# FPOSINDC3.net
KiCad netlist of a schematic drawn in Altium Designer
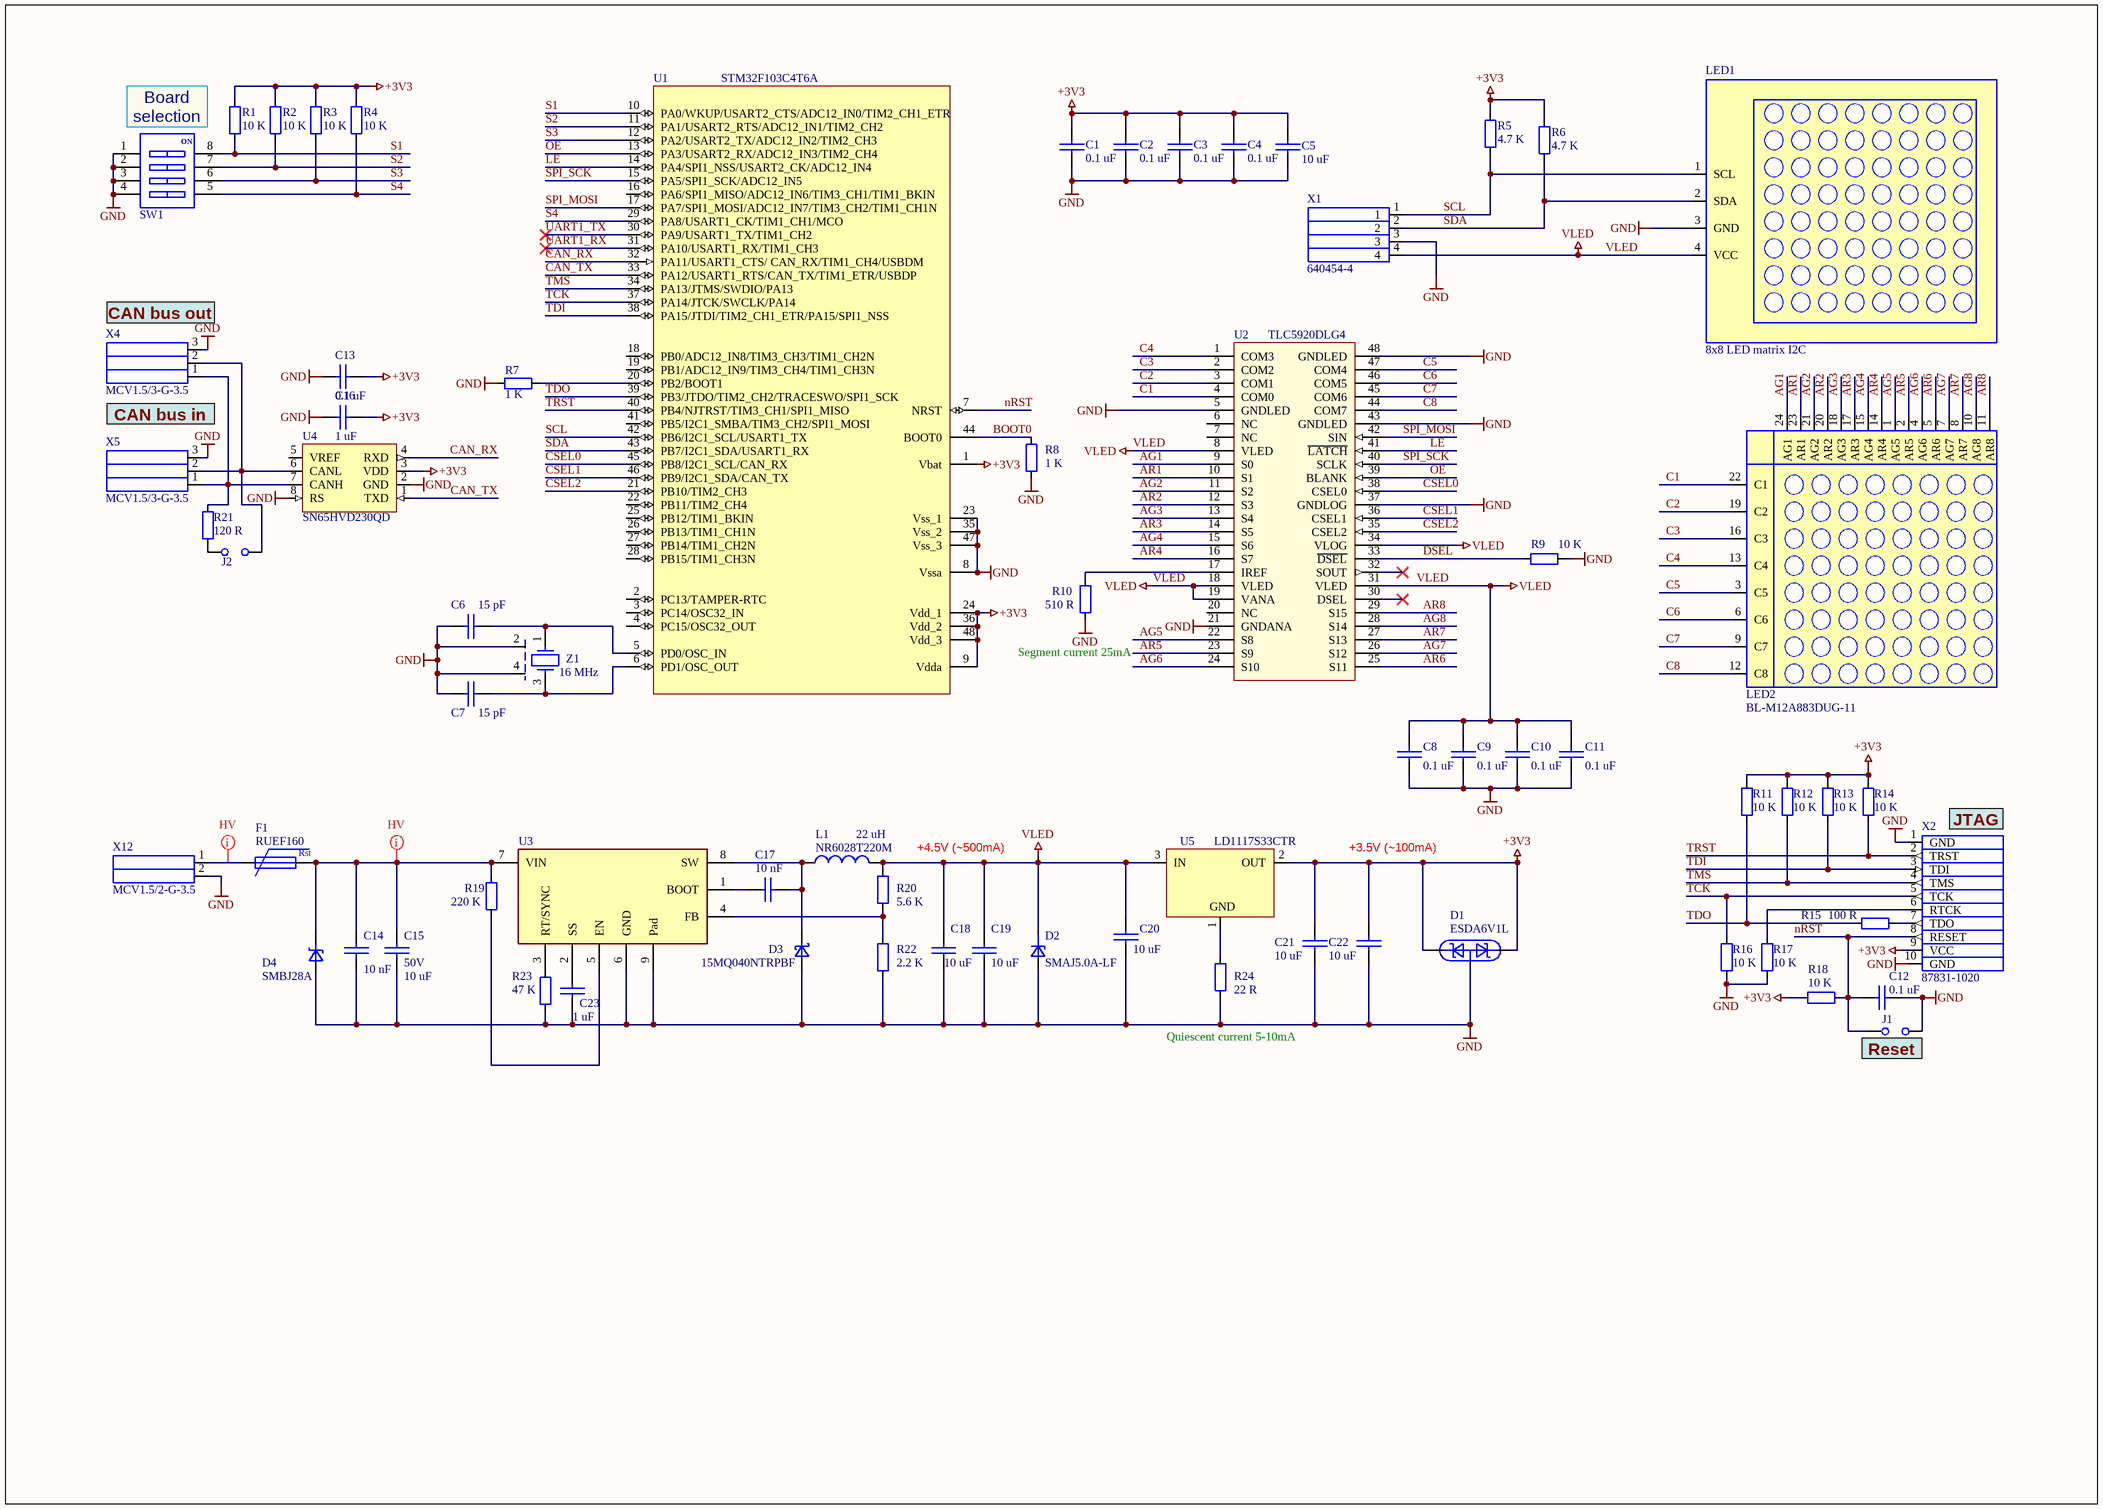
[diagram p0: FPOSINDC3.SchDoc]

(export (version "E")
  (design (tool "Eeschema 10.0.6"))
  (components
    (comp (ref "C1")
      (value "0.1 uF")
      (footprint "1608[0603]")
      (description "0.1 uF, 50V, 10% , X7R,  0603 SMD MLC Capacitor")
      (fields (field (name "TOLERANCE") "± 10%") (field (name "MANUFACTURER") "WALSIN"))
      (libsource (lib "ea_Capacitors") (part "CVNF100K0603-25"))
    )
    (comp (ref "C2")
      (value "0.1 uF")
      (footprint "1608[0603]")
      (description "0.1 uF, 50V, 10% , X7R,  0603 SMD MLC Capacitor")
      (fields (field (name "TOLERANCE") "± 10%") (field (name "MANUFACTURER") "WALSIN"))
      (libsource (lib "ea_Capacitors") (part "CVNF100K0603-25"))
    )
    (comp (ref "C3")
      (value "0.1 uF")
      (footprint "1608[0603]")
      (description "0.1 uF, 50V, 10% , X7R,  0603 SMD MLC Capacitor")
      (fields (field (name "TOLERANCE") "± 10%") (field (name "MANUFACTURER") "WALSIN"))
      (libsource (lib "ea_Capacitors") (part "CVNF100K0603-25"))
    )
    (comp (ref "C4")
      (value "0.1 uF")
      (footprint "1608[0603]")
      (description "0.1 uF, 50V, 10% , X7R,  0603 SMD MLC Capacitor")
      (fields (field (name "TOLERANCE") "± 10%") (field (name "MANUFACTURER") "WALSIN"))
      (libsource (lib "ea_Capacitors") (part "CVNF100K0603-25"))
    )
    (comp (ref "C5")
      (value "10 uF")
      (footprint "2012[0805]")
      (description "10 uF, 25V, X5R, ±10%, 0805")
      (fields (field (name "MANUFACTURER") "AVX Corporation") (field (name "TOLERANCE") "±10%"))
      (libsource (lib "ea_Capacitors") (part "GRM21BR60J106KE19L"))
    )
    (comp (ref "C6")
      (value "15 pF")
      (footprint "1608[0603]")
      (description "15 pF, 50V, 5%, NP0, 0603 SMD MLC Capacitor")
      (fields (field (name "MANUFACTURER") "Darfon") (field (name "TOLERANCE") "5%"))
      (libsource (lib "ea_Capacitors") (part "CCPF015K0603"))
    )
    (comp (ref "C7")
      (value "15 pF")
      (footprint "1608[0603]")
      (description "15 pF, 50V, 5%, NP0, 0603 SMD MLC Capacitor")
      (fields (field (name "MANUFACTURER") "Darfon") (field (name "TOLERANCE") "5%"))
      (libsource (lib "ea_Capacitors") (part "CCPF015K0603"))
    )
    (comp (ref "C8")
      (value "0.1 uF")
      (footprint "1608[0603]")
      (description "0.1 uF, 50V, 10% , X7R,  0603 SMD MLC Capacitor")
      (fields (field (name "TOLERANCE") "± 10%") (field (name "MANUFACTURER") "WALSIN"))
      (libsource (lib "ea_Capacitors") (part "CVNF100K0603-25"))
    )
    (comp (ref "C9")
      (value "0.1 uF")
      (footprint "1608[0603]")
      (description "0.1 uF, 50V, 10% , X7R,  0603 SMD MLC Capacitor")
      (fields (field (name "TOLERANCE") "± 10%") (field (name "MANUFACTURER") "WALSIN"))
      (libsource (lib "ea_Capacitors") (part "CVNF100K0603-25"))
    )
    (comp (ref "C10")
      (value "0.1 uF")
      (footprint "1608[0603]")
      (description "0.1 uF, 50V, 10% , X7R,  0603 SMD MLC Capacitor")
      (fields (field (name "TOLERANCE") "± 10%") (field (name "MANUFACTURER") "WALSIN"))
      (libsource (lib "ea_Capacitors") (part "CVNF100K0603-25"))
    )
    (comp (ref "C11")
      (value "0.1 uF")
      (footprint "1608[0603]")
      (description "0.1 uF, 50V, 10% , X7R,  0603 SMD MLC Capacitor")
      (fields (field (name "TOLERANCE") "± 10%") (field (name "MANUFACTURER") "WALSIN"))
      (libsource (lib "ea_Capacitors") (part "CVNF100K0603-25"))
    )
    (comp (ref "C12")
      (value "0.1 uF")
      (footprint "1608[0603]")
      (description "0.1 uF, 50V, 10% , X7R,  0603 SMD MLC Capacitor")
      (fields (field (name "TOLERANCE") "± 10%") (field (name "MANUFACTURER") "WALSIN"))
      (libsource (lib "ea_Capacitors") (part "CVNF100K0603-25"))
    )
    (comp (ref "C13")
      (value "0.1 uF")
      (footprint "1608[0603]")
      (description "0.1 uF, 50V, 10% , X7R,  0603 SMD MLC Capacitor")
      (fields (field (name "TOLERANCE") "± 10%") (field (name "MANUFACTURER") "WALSIN"))
      (libsource (lib "ea_Capacitors") (part "CVNF100K0603-25"))
    )
    (comp (ref "C14")
      (value "10 nF")
      (footprint "1608[0603]")
      (description "10 nF, 100V, 10%, X7R, 0603 SMD MLC Capacitor")
      (fields (field (name "MANUFACTURER") "SAMSUNG") (field (name "TOLERANCE") "±10%"))
      (libsource (lib "ea_Capacitors") (part "CVNF010K0603"))
    )
    (comp (ref "C15")
      (value "10 uF")
      (footprint "3225[1210]")
      (description "10uF, 50V, 20%, Y5V (F), 1210")
      (fields
        (field (name "MANUFACTURER") "Murata Electronics North America")
        (field (name "TOLERANCE") "20%")
        (field (name "VOLTAGE") "50V")
      )
      (libsource (lib "ea_Capacitors") (part "GRM32DF51H106ZA01L"))
    )
    (comp (ref "C16")
      (value "1 uF")
      (footprint "2012[0805]")
      (description "1 uF, 50V, 10%, X7R, 0805")
      (fields (field (name "MANUFACTURER") "KEMET") (field (name "TOLERANCE") "± 10%"))
      (libsource (lib "ea_Capacitors") (part "CVUF001K0805"))
    )
    (comp (ref "C17")
      (value "10 nF")
      (footprint "1608[0603]")
      (description "10 nF, 100V, 10%, X7R, 0603 SMD MLC Capacitor")
      (fields (field (name "TOLERANCE") "±10%") (field (name "MANUFACTURER") "SAMSUNG"))
      (libsource (lib "ea_Capacitors") (part "CVNF010K0603"))
    )
    (comp (ref "C18")
      (value "10 uF")
      (footprint "2012[0805]")
      (description "10 uF, 25V, X5R, ±10%, 0805")
      (fields (field (name "MANUFACTURER") "AVX Corporation") (field (name "TOLERANCE") "±10%"))
      (libsource (lib "ea_Capacitors") (part "LMK212F106ZG-T"))
    )
    (comp (ref "C19")
      (value "10 uF")
      (footprint "2012[0805]")
      (description "10 uF, 25V, X5R, ±10%, 0805")
      (fields (field (name "MANUFACTURER") "AVX Corporation") (field (name "TOLERANCE") "±10%"))
      (libsource (lib "ea_Capacitors") (part "LMK212F106ZG-T"))
    )
    (comp (ref "C20")
      (value "10 uF")
      (footprint "2012[0805]")
      (description "10 uF, 25V, X5R, ±10%, 0805")
      (fields (field (name "MANUFACTURER") "AVX Corporation") (field (name "TOLERANCE") "±10%"))
      (libsource (lib "ea_Capacitors") (part "LMK212F106ZG-T"))
    )
    (comp (ref "C21")
      (value "10 uF")
      (footprint "2012[0805]")
      (description "10 uF, 25V, X5R, ±10%, 0805")
      (fields (field (name "MANUFACTURER") "AVX Corporation") (field (name "TOLERANCE") "±10%"))
      (libsource (lib "ea_Capacitors") (part "LMK212F106ZG-T"))
    )
    (comp (ref "C22")
      (value "10 uF")
      (footprint "2012[0805]")
      (description "10 uF, 25V, X5R, ±10%, 0805")
      (fields (field (name "MANUFACTURER") "AVX Corporation") (field (name "TOLERANCE") "±10%"))
      (libsource (lib "ea_Capacitors") (part "LMK212F106ZG-T"))
    )
    (comp (ref "C23")
      (value "1 uF")
      (footprint "2012[0805]")
      (description "1 uF, 50V, 10%, X7R, 0805")
      (fields (field (name "MANUFACTURER") "KEMET") (field (name "TOLERANCE") "± 10%"))
      (libsource (lib "ea_Capacitors") (part "GRM21BR71A105KA01L"))
    )
    (comp (ref "D1")
      (value "ESDA6V1L")
      (footprint "SOT23")
      (description "Dual transil array for ESD, 6.1 V, 300 W")
      (fields (field (name "MANUFACTURER") "ST") (field (name "PARTNUM") "511-ESDA6V1L"))
      (libsource (lib "*") (part "ESDA6V1L"))
    )
    (comp (ref "D2")
      (value "SMAJ5.0A-LF")
      (footprint "DO-214AA_SMBJ")
      (description "TVS 400W 5.0V Unidirect")
      (fields (field (name "MANUFACTURER") "LITTELFUSE"))
      (libsource (lib "ea_TVS_protection") (part "SMAJ5.0A-LF"))
    )
    (comp (ref "D3")
      (value "15MQ040NTRPBF")
      (footprint "SMA")
      (description "Schottky Power Rectifier 3A, 40V, SMA")
      (fields (field (name "MANUFACTURER") "VISHAY"))
      (libsource (lib "ea_Diodes") (part "15MQ040N"))
    )
    (comp (ref "D4")
      (value "SMBJ28A")
      (footprint "DO-214AA_SMBJ")
      (description "DIODE TVS 28V 600W UNI 5% SMD")
      (fields (field (name "MANUFACTURER") "Littelfuse") (field (name "PARTNUM") "SMBJ28ABCT-ND"))
      (libsource (lib "ea_TVS_protection") (part "SMBJ28A"))
    )
    (comp (ref "F1")
      (value "RUEF160")
      (footprint "RUE160")
      (description "RUEF160 - POLYSWITCH, RADIAL, 1.6A")
      (fields (field (name "MANUFACTURER") "RAYCHEM") (field (name "PARTNUM") "RUEF160-ND"))
      (libsource (lib "ea_Fuses") (part "RUEF160"))
    )
    (comp (ref "J1")
      (value "Jumper")
      (footprint "HDR1X2V")
      (fields (field (name "MANUFACTURER") "NINIGI") (field (name "PARTNUM") "JUMPER-B"))
      (libsource (lib "ea_Commutation") (part "Jumper"))
    )
    (comp (ref "J2")
      (value "Jumper")
      (footprint "HDR1X2V")
      (fields (field (name "MANUFACTURER") "NINIGI") (field (name "PARTNUM") "JUMPER-B"))
      (libsource (lib "ea_Commutation") (part "Jumper"))
    )
    (comp (ref "L1")
      (value "NR6028T220M")
      (footprint "NR6028 yuden")
      (description "22uH, 1.3 A, 0.175 Ohms, +-20%,- 25 C to + 120 C")
      (fields
        (field (name "MANUFACTURER") "Taiyo Yuden")
        (field (name "PARTNUM") "587-2103-1-ND")
        (field (name "ALTIUM_VALUE") "22 uH")
      )
      (libsource (lib "ea_Inductors") (part "NR6028T220M"))
    )
    (comp (ref "LED1")
      (value "8x8 LED matrix I2C")
      (footprint "I2C 8x8 matrix adafruit 902")
      (description "Adafruit Bicolor LED Square Pixel Matrix with I2C Backpack")
      (fields (field (name "MANUFACTURER") "Adafruit") (field (name "PARTNUM") "ID: 902"))
      (libsource (lib "ea_Indicators") (part "8x8 LED matrix I2C"))
    )
    (comp (ref "LED2")
      (value "BL-M12A883DUG-11")
      (footprint "BL_M12A883DUG-11")
      (description "DOTMATRIX DISPLAY row catode red/green 8x8 31.7x31.7mm; Imax 30mA")
      (fields (field (name "MANUFACTURER") "BetLuxs"))
      (libsource (lib "ea_Indicators") (part "BL-M12A883DUG-11"))
    )
    (comp (ref "R1")
      (value "10 K")
      (footprint "0603")
      (description "10 K, 1%, 0603, SMD Resistor, Taped")
      (fields (field (name "MANUFACTURER") "YAGEO") (field (name "TOLERANCE") "± 1%"))
      (libsource (lib "") (part "RL0603K010-1_1"))
    )
    (comp (ref "R2")
      (value "10 K")
      (footprint "0603")
      (description "10 K, 1%, 0603, SMD Resistor, Taped")
      (fields (field (name "MANUFACTURER") "YAGEO") (field (name "TOLERANCE") "± 1%"))
      (libsource (lib "") (part "RL0603K010-1_1"))
    )
    (comp (ref "R3")
      (value "10 K")
      (footprint "0603")
      (description "10 K, 1%, 0603, SMD Resistor, Taped")
      (fields (field (name "MANUFACTURER") "YAGEO") (field (name "TOLERANCE") "± 1%"))
      (libsource (lib "") (part "RL0603K010-1_1"))
    )
    (comp (ref "R4")
      (value "10 K")
      (footprint "0603")
      (description "10 K, 1%, 0603, SMD Resistor, Taped")
      (fields (field (name "MANUFACTURER") "YAGEO") (field (name "TOLERANCE") "± 1%"))
      (libsource (lib "") (part "RL0603K010-1_1"))
    )
    (comp (ref "R5")
      (value "4.7 K")
      (footprint "0603")
      (description "4.7 K, 1%, 0603, SMD Resistor, Taped")
      (fields (field (name "MANUFACTURER") "Vishay") (field (name "TOLERANCE") "1%"))
      (libsource (lib "ea_Resistors") (part "RL0603K004.7-1"))
    )
    (comp (ref "R6")
      (value "4.7 K")
      (footprint "0603")
      (description "4.7 K, 1%, 0603, SMD Resistor, Taped")
      (fields (field (name "MANUFACTURER") "Vishay") (field (name "TOLERANCE") "1%"))
      (libsource (lib "ea_Resistors") (part "RL0603K004.7-1"))
    )
    (comp (ref "R7")
      (value "1 K")
      (footprint "0603")
      (description "1 K, 1%, 0603, SMD Resistor, Taped")
      (fields (field (name "MANUFACTURER") "Vishay") (field (name "TOLERANCE") "1%"))
      (libsource (lib "ea_Resistors") (part "RL0603K001-1"))
    )
    (comp (ref "R8")
      (value "1 K")
      (footprint "0603")
      (description "1 K, 1%, 0603, SMD Resistor, Taped")
      (fields (field (name "MANUFACTURER") "Vishay") (field (name "TOLERANCE") "1%"))
      (libsource (lib "") (part "RL0603K001-1_1"))
    )
    (comp (ref "R9")
      (value "10 K")
      (footprint "0603")
      (description "10 K, 1%, 0603, SMD Resistor, Taped")
      (fields (field (name "MANUFACTURER") "YAGEO") (field (name "TOLERANCE") "± 1%"))
      (libsource (lib "") (part "RL0603K010-1_2"))
    )
    (comp (ref "R10")
      (value "510 R")
      (footprint "0603")
      (description "510 R, 1%, 0603, SMD Resistor, Taped")
      (fields (field (name "MANUFACTURER") "Vishay") (field (name "TOLERANCE") "1%"))
      (libsource (lib "ea_Resistors") (part "RL0603E510-1"))
    )
    (comp (ref "R11")
      (value "10 K")
      (footprint "0603")
      (description "10 K, 1%, 0603, SMD Resistor, Taped")
      (fields (field (name "MANUFACTURER") "YAGEO") (field (name "TOLERANCE") "± 1%"))
      (libsource (lib "ea_Resistors") (part "RL0603K010-1"))
    )
    (comp (ref "R12")
      (value "10 K")
      (footprint "0603")
      (description "10 K, 1%, 0603, SMD Resistor, Taped")
      (fields (field (name "MANUFACTURER") "YAGEO") (field (name "TOLERANCE") "± 1%"))
      (libsource (lib "ea_Resistors") (part "RL0603K010-1"))
    )
    (comp (ref "R13")
      (value "10 K")
      (footprint "0603")
      (description "10 K, 1%, 0603, SMD Resistor, Taped")
      (fields (field (name "MANUFACTURER") "YAGEO") (field (name "TOLERANCE") "± 1%"))
      (libsource (lib "ea_Resistors") (part "RL0603K010-1"))
    )
    (comp (ref "R14")
      (value "10 K")
      (footprint "0603")
      (description "10 K, 1%, 0603, SMD Resistor, Taped")
      (fields (field (name "MANUFACTURER") "YAGEO") (field (name "TOLERANCE") "± 1%"))
      (libsource (lib "ea_Resistors") (part "RL0603K010-1"))
    )
    (comp (ref "R15")
      (value "100 R")
      (footprint "0603")
      (description "100 R, 1%, 0603, SMD Resistor, Taped")
      (fields (field (name "MANUFACTURER") "Vishay") (field (name "TOLERANCE") "1%"))
      (libsource (lib "ea_Resistors") (part "RL0603E100-1"))
    )
    (comp (ref "R16")
      (value "10 K")
      (footprint "0603")
      (description "10 K, 1%, 0603, SMD Resistor, Taped")
      (fields (field (name "MANUFACTURER") "YAGEO") (field (name "TOLERANCE") "± 1%"))
      (libsource (lib "ea_Resistors") (part "RL0603K010-1"))
    )
    (comp (ref "R17")
      (value "10 K")
      (footprint "0603")
      (description "10 K, 1%, 0603, SMD Resistor, Taped")
      (fields (field (name "MANUFACTURER") "YAGEO") (field (name "TOLERANCE") "± 1%"))
      (libsource (lib "ea_Resistors") (part "RL0603K010-1"))
    )
    (comp (ref "R18")
      (value "10 K")
      (footprint "0603")
      (description "10 K, 1%, 0603, SMD Resistor, Taped")
      (fields (field (name "MANUFACTURER") "YAGEO") (field (name "TOLERANCE") "± 1%"))
      (libsource (lib "") (part "RL0603K010-1_2"))
    )
    (comp (ref "R19")
      (value "220 K")
      (footprint "0603")
      (description "220 K, 1%, 0603, SMD Resistor, Taped")
      (fields (field (name "MANUFACTURER") "YAGEO AMERICA CORPORATION") (field (name "TOLERANCE") "1%"))
      (libsource (lib "ea_Resistors") (part "RL0603K220-1_1"))
    )
    (comp (ref "R20")
      (value "5.6 K")
      (footprint "0603")
      (description "5.6 K, 1%, 0603, SMD Resistor, Taped")
      (fields (field (name "MANUFACTURER") "Vishay") (field (name "TOLERANCE") "1%"))
      (libsource (lib "ea_Resistors") (part "RL0603K005.6-1"))
    )
    (comp (ref "R21")
      (value "120 R")
      (footprint "0603")
      (description "120 R, 1%, 0603, SMD Resistor, Taped")
      (fields (field (name "MANUFACTURER") "Vishay") (field (name "TOLERANCE") "1%"))
      (libsource (lib "ea_Resistors") (part "RL0603E120-1"))
    )
    (comp (ref "R22")
      (value "2.2 K")
      (footprint "0603")
      (description "2.2 K, 1%, 0603, SMD Resistor, Taped")
      (fields (field (name "MANUFACTURER") "Vishay") (field (name "TOLERANCE") "1%"))
      (libsource (lib "ea_Resistors") (part "RL0603K002.2-1"))
    )
    (comp (ref "R23")
      (value "47 K")
      (footprint "0603")
      (description "47 K, 1%, 0603, SMD Resistor, Taped")
      (fields (field (name "MANUFACTURER") "YAGEO AMERICA CORPORATION") (field (name "TOLERANCE") "1%"))
      (libsource (lib "ea_Resistors") (part "RC0603FR-0747KL"))
    )
    (comp (ref "R24")
      (value "22 R")
      (footprint "0603")
      (description "22 R, 1%, 0603, SMD Resistor, Taped")
      (fields (field (name "MANUFACTURER") "Vishay") (field (name "TOLERANCE") "1%"))
      (libsource (lib "ea_Resistors") (part "RL0603E022-1"))
    )
    (comp (ref "SW1")
      (value "MCDHN-04F-T-V")
      (footprint "MCDHN-04F-T-V")
      (description "SWITCH, DIP, SMD, 4 WAY, 1.27mm")
      (fields (field (name "MANUFACTURER") "MULTICOMP") (field (name "PARTNUM") "1605479"))
      (libsource (lib "ea_Commutation") (part "MCDHN-04F-T-V"))
    )
    (comp (ref "U1")
      (value "STM32F103C4T6A")
      (footprint "LQFP-48")
      (description "MCU ARM 32BIT 16K FLASH 48-LQFP")
      (fields (field (name "MANUFACTURER") "STMicroelectronics") (field (name "PARTNUM") "497-8316-ND"))
      (libsource (lib "ea_CPU") (part "STM32F103C4T6A"))
    )
    (comp (ref "U2")
      (value "TLC5920DLG4")
      (footprint "DL048")
      (description "16X8BIT LED DRIVER/CONTRLR, SSOP48")
      (fields (field (name "MANUFACTURER") "TI") (field (name "PARTNUM") "1226302"))
      (libsource (lib "ea_IC_registers_buffers") (part "TLC5920DLG4"))
    )
    (comp (ref "U3")
      (value "~")
      (footprint "SOIC-8 EDP")
      (description "SIMPLESWITCH, 1.0A 4.5~42VIN, 8PSOP, Vf 1.285")
      (fields (field (name "MANUFACTURER") "TI") (field (name "PARTNUM") "2323524"))
      (libsource (lib "ea_IC_Power_Reg_Ref_Sw") (part "LM22672MR-ADJ"))
    )
    (comp (ref "U4")
      (value "SN65HVD230QD")
      (footprint "SO-8")
      (description "3.3-V CAN TRANSCEIVERS SO-8")
      (fields (field (name "MANUFACTURER") "Texas Instruments") (field (name "PARTNUM") "296-13123-5-ND"))
      (libsource (lib "ea_IC_Interfaces") (part "SN65HVD230QD"))
    )
    (comp (ref "U5")
      (value "LD1117S33CTR")
      (footprint "SOT-223")
      (description "Low drop positive voltage regulator, 3.3 V, 1A, SOT-223")
      (fields (field (name "MANUFACTURER") "STMicroelectronics") (field (name "PARTNUM") "497-1241-1-ND"))
      (libsource (lib "ea_IC_Power_Reg_Ref_Sw") (part "LD1117S33CTR"))
    )
    (comp (ref "X1")
      (value "640454-4")
      (footprint "MTA-100 4-pos")
      (description "CONN HEADER VERT 4POS .100 TIN")
      (fields (field (name "MANUFACTURER") "TE Connectivity") (field (name "PARTNUM") "A19431-ND"))
      (libsource (lib "ea_Connectors") (part "640454-4"))
    )
    (comp (ref "X2")
      (value "87831-1020")
      (footprint "878311020 MGRID WALL HDR")
      (description "JTAG 2*5 2mm")
      (fields
        (field (name "MANUFACTURER") "Molex/Waldom Electronics Corp")
        (field (name "PARTNUM") "WM18560-ND")
      )
      (libsource (lib "ea_Connectors") (part "87831-1020"))
    )
    (comp (ref "X4")
      (value "MCV1.5/3-G-3.5")
      (footprint "mcv1.5-3-g_3.5")
      (description "HEADER, VERTICAL, 3.5MM, 3WAY")
      (fields (field (name "MANUFACTURER") "PHOENIX CONTACT") (field (name "PARTNUM") "3704828"))
      (libsource (lib "ea_Connectors") (part "MCV1.5/3-G-3.5"))
    )
    (comp (ref "X5")
      (value "MCV1.5/3-G-3.5")
      (footprint "mcv1.5-3-g_3.5")
      (description "HEADER, VERTICAL, 3.5MM, 3WAY")
      (fields (field (name "MANUFACTURER") "PHOENIX CONTACT") (field (name "PARTNUM") "3704828"))
      (libsource (lib "ea_Connectors") (part "MCV1.5/3-G-3.5"))
    )
    (comp (ref "X12")
      (value "MCV1.5/2-G-3.5")
      (footprint "mcv1.5-2-g_3.5")
      (description "HEADER, VERTICAL, 3.5MM, 2WAY")
      (fields (field (name "MANUFACTURER") "PHOENIX CONTACT") (field (name "PARTNUM") "3704816"))
      (libsource (lib "ea_Connectors") (part "MCV1.5/2-G-3.5"))
    )
    (comp (ref "Z1")
      (value "16 MHz")
      (footprint "DSX321G")
      (description "16 MHz, 8 pF, +-15 ppm, -10..+75 С")
      (fields (field (name "MANUFACTURER") "NDK") (field (name "PARTNUM") "644-1049-1-ND"))
      (libsource (lib "ea_OSC_CLK_GEN") (part "NX3225SA-16.0MHZ"))
    )
  )
  (nets
    (net (code "1") (name "+3V3") (class "Default")
      (node (ref "C1") (pin "2") (pinfunction "2_2") (pintype "passive"))
      (node (ref "C13") (pin "1") (pinfunction "1_1") (pintype "passive"))
      (node (ref "C16") (pin "1") (pinfunction "1_1") (pintype "passive"))
      (node (ref "C2") (pin "2") (pinfunction "2_2") (pintype "passive"))
      (node (ref "C21") (pin "2") (pinfunction "2_2") (pintype "passive"))
      (node (ref "C22") (pin "2") (pinfunction "2_2") (pintype "passive"))
      (node (ref "C3") (pin "2") (pinfunction "2_2") (pintype "passive"))
      (node (ref "C4") (pin "2") (pinfunction "2_2") (pintype "passive"))
      (node (ref "C5") (pin "2") (pinfunction "2_2") (pintype "passive"))
      (node (ref "D1") (pin "1") (pintype "passive"))
      (node (ref "D1") (pin "2") (pintype "passive"))
      (node (ref "R1") (pin "2") (pinfunction "2_2") (pintype "passive"))
      (node (ref "R11") (pin "1") (pinfunction "1_1") (pintype "passive"))
      (node (ref "R12") (pin "1") (pinfunction "1_1") (pintype "passive"))
      (node (ref "R13") (pin "1") (pinfunction "1_1") (pintype "passive"))
      (node (ref "R14") (pin "1") (pinfunction "1_1") (pintype "passive"))
      (node (ref "R18") (pin "1") (pinfunction "1_1") (pintype "passive"))
      (node (ref "R2") (pin "2") (pinfunction "2_2") (pintype "passive"))
      (node (ref "R3") (pin "2") (pinfunction "2_2") (pintype "passive"))
      (node (ref "R4") (pin "2") (pinfunction "2_2") (pintype "passive"))
      (node (ref "R5") (pin "1") (pinfunction "1_1") (pintype "passive"))
      (node (ref "R6") (pin "1") (pinfunction "1_1") (pintype "passive"))
      (node (ref "U1") (pin "1") (pinfunction "Vbat_1") (pintype "power_in"))
      (node (ref "U1") (pin "24") (pinfunction "Vdd_1_24") (pintype "power_in"))
      (node (ref "U1") (pin "36") (pinfunction "Vdd_2_36") (pintype "power_in"))
      (node (ref "U1") (pin "48") (pinfunction "Vdd_3_48") (pintype "power_in"))
      (node (ref "U1") (pin "9") (pinfunction "Vdda_9") (pintype "passive"))
      (node (ref "U4") (pin "3") (pinfunction "VDD_3") (pintype "power_in"))
      (node (ref "U5") (pin "2") (pinfunction "OUT_2") (pintype "power_in"))
      (node (ref "X2") (pin "9") (pinfunction "VCC_9") (pintype "power_in"))
    )
    (net (code "2") (name "/AG1") (class "Default")
      (node (ref "LED2") (pin "24") (pinfunction "AG1_24") (pintype "passive"))
      (node (ref "U2") (pin "9") (pinfunction "S0_9") (pintype "power_in"))
    )
    (net (code "3") (name "/AG2") (class "Default")
      (node (ref "LED2") (pin "21") (pinfunction "AG2_21") (pintype "passive"))
      (node (ref "U2") (pin "11") (pinfunction "S2_11") (pintype "power_in"))
    )
    (net (code "4") (name "/AG3") (class "Default")
      (node (ref "LED2") (pin "18") (pinfunction "AG3_18") (pintype "passive"))
      (node (ref "U2") (pin "13") (pinfunction "S4_13") (pintype "power_in"))
    )
    (net (code "5") (name "/AG4") (class "Default")
      (node (ref "LED2") (pin "15") (pinfunction "AG4_15") (pintype "passive"))
      (node (ref "U2") (pin "15") (pinfunction "S6_15") (pintype "power_in"))
    )
    (net (code "6") (name "/AG5") (class "Default")
      (node (ref "LED2") (pin "1") (pinfunction "AG5_1") (pintype "passive"))
      (node (ref "U2") (pin "22") (pinfunction "S8_22") (pintype "power_in"))
    )
    (net (code "7") (name "/AG6") (class "Default")
      (node (ref "LED2") (pin "4") (pinfunction "AG6_4") (pintype "passive"))
      (node (ref "U2") (pin "24") (pinfunction "S10_24") (pintype "power_in"))
    )
    (net (code "8") (name "/AG7") (class "Default")
      (node (ref "LED2") (pin "7") (pinfunction "AG7_7") (pintype "passive"))
      (node (ref "U2") (pin "26") (pinfunction "S12_26") (pintype "power_in"))
    )
    (net (code "9") (name "/AG8") (class "Default")
      (node (ref "LED2") (pin "10") (pinfunction "AG8_10") (pintype "passive"))
      (node (ref "U2") (pin "28") (pinfunction "S14_28") (pintype "power_in"))
    )
    (net (code "10") (name "/AR1") (class "Default")
      (node (ref "LED2") (pin "23") (pinfunction "AR1_23") (pintype "passive"))
      (node (ref "U2") (pin "10") (pinfunction "S1_10") (pintype "power_in"))
    )
    (net (code "11") (name "/AR2") (class "Default")
      (node (ref "LED2") (pin "20") (pinfunction "AR2_20") (pintype "passive"))
      (node (ref "U2") (pin "12") (pinfunction "S3_12") (pintype "power_in"))
    )
    (net (code "12") (name "/AR3") (class "Default")
      (node (ref "LED2") (pin "17") (pinfunction "AR3_17") (pintype "passive"))
      (node (ref "U2") (pin "14") (pinfunction "S5_14") (pintype "power_in"))
    )
    (net (code "13") (name "/AR4") (class "Default")
      (node (ref "LED2") (pin "14") (pinfunction "AR4_14") (pintype "passive"))
      (node (ref "U2") (pin "16") (pinfunction "S7_16") (pintype "power_in"))
    )
    (net (code "14") (name "/AR5") (class "Default")
      (node (ref "LED2") (pin "2") (pinfunction "AR5_2") (pintype "passive"))
      (node (ref "U2") (pin "23") (pinfunction "S9_23") (pintype "power_in"))
    )
    (net (code "15") (name "/AR6") (class "Default")
      (node (ref "LED2") (pin "5") (pinfunction "AR6_5") (pintype "passive"))
      (node (ref "U2") (pin "25") (pinfunction "S11_25") (pintype "power_in"))
    )
    (net (code "16") (name "/AR7") (class "Default")
      (node (ref "LED2") (pin "8") (pinfunction "AR7_8") (pintype "passive"))
      (node (ref "U2") (pin "27") (pinfunction "S13_27") (pintype "power_in"))
    )
    (net (code "17") (name "/AR8") (class "Default")
      (node (ref "LED2") (pin "11") (pinfunction "AR8_11") (pintype "passive"))
      (node (ref "U2") (pin "29") (pinfunction "S15_29") (pintype "power_in"))
    )
    (net (code "18") (name "/BOOT0") (class "Default")
      (node (ref "R8") (pin "2") (pinfunction "2_2") (pintype "passive"))
      (node (ref "U1") (pin "44") (pinfunction "BOOT0_44") (pintype "passive"))
    )
    (net (code "19") (name "/C1") (class "Default")
      (node (ref "LED2") (pin "22") (pinfunction "C1_22") (pintype "passive"))
      (node (ref "U2") (pin "4") (pinfunction "COM0_4") (pintype "power_in"))
    )
    (net (code "20") (name "/C2") (class "Default")
      (node (ref "LED2") (pin "19") (pinfunction "C2_19") (pintype "passive"))
      (node (ref "U2") (pin "3") (pinfunction "COM1_3") (pintype "power_in"))
    )
    (net (code "21") (name "/C3") (class "Default")
      (node (ref "LED2") (pin "16") (pinfunction "C3_16") (pintype "passive"))
      (node (ref "U2") (pin "2") (pinfunction "COM2_2") (pintype "power_in"))
    )
    (net (code "22") (name "/C4") (class "Default")
      (node (ref "LED2") (pin "13") (pinfunction "C4_13") (pintype "passive"))
      (node (ref "U2") (pin "1") (pinfunction "COM3_1") (pintype "power_in"))
    )
    (net (code "23") (name "/C5") (class "Default")
      (node (ref "LED2") (pin "3") (pinfunction "C5_3") (pintype "passive"))
      (node (ref "U2") (pin "47") (pinfunction "COM4_47") (pintype "power_in"))
    )
    (net (code "24") (name "/C6") (class "Default")
      (node (ref "LED2") (pin "6") (pinfunction "C6_6") (pintype "passive"))
      (node (ref "U2") (pin "46") (pinfunction "COM5_46") (pintype "power_in"))
    )
    (net (code "25") (name "/C7") (class "Default")
      (node (ref "LED2") (pin "9") (pinfunction "C7_9") (pintype "passive"))
      (node (ref "U2") (pin "45") (pinfunction "COM6_45") (pintype "power_in"))
    )
    (net (code "26") (name "/C8") (class "Default")
      (node (ref "LED2") (pin "12") (pinfunction "C8_12") (pintype "passive"))
      (node (ref "U2") (pin "44") (pinfunction "COM7_44") (pintype "power_in"))
    )
    (net (code "27") (name "/CAN_RX") (class "Default")
      (node (ref "U1") (pin "32") (pinfunction "PA11/USART1_CTS/_CAN_RX/TIM1_CH4/USBDM_32") (pintype "input"))
      (node (ref "U4") (pin "4") (pinfunction "RXD_4") (pintype "output"))
    )
    (net (code "28") (name "/CAN_TX") (class "Default")
      (node (ref "U1") (pin "33") (pinfunction "PA12/USART1_RTS/CAN_TX/TIM1_ETR/USBDP_33") (pintype "bidirectional"))
      (node (ref "U4") (pin "1") (pinfunction "TXD_1") (pintype "input"))
    )
    (net (code "29") (name "/CSEL0") (class "Default")
      (node (ref "U1") (pin "45") (pinfunction "PB8/I2C1_SCL/CAN_RX_45") (pintype "bidirectional"))
      (node (ref "U2") (pin "38") (pinfunction "CSEL0_38") (pintype "input"))
    )
    (net (code "30") (name "/CSEL1") (class "Default")
      (node (ref "U1") (pin "46") (pinfunction "PB9/I2C1_SDA/CAN_TX_46") (pintype "bidirectional"))
      (node (ref "U2") (pin "36") (pinfunction "CSEL1_36") (pintype "input"))
    )
    (net (code "31") (name "/CSEL2") (class "Default")
      (node (ref "U1") (pin "21") (pinfunction "PB10/TIM2_CH3_21") (pintype "bidirectional"))
      (node (ref "U2") (pin "35") (pinfunction "CSEL2_35") (pintype "input"))
    )
    (net (code "32") (name "/DSEL") (class "Default")
      (node (ref "R9") (pin "1") (pinfunction "1_1") (pintype "passive"))
      (node (ref "U2") (pin "33") (pinfunction "~{DSEL}_33") (pintype "passive"))
    )
    (net (code "33") (name "/LE") (class "Default")
      (node (ref "U1") (pin "14") (pinfunction "PA4/SPI1_NSS/USART2_CK/ADC12_IN4_14") (pintype "bidirectional"))
      (node (ref "U2") (pin "41") (pinfunction "~{LATCH}_41") (pintype "input"))
    )
    (net (code "34") (name "/OE") (class "Default")
      (node (ref "U1") (pin "13") (pinfunction "PA3/USART2_RX/ADC12_IN3/TIM2_CH4_13") (pintype "bidirectional"))
      (node (ref "U2") (pin "39") (pinfunction "BLANK_39") (pintype "input"))
    )
    (net (code "35") (name "/S1") (class "Default")
      (node (ref "R1") (pin "1") (pinfunction "1_1") (pintype "passive"))
      (node (ref "SW1") (pin "8") (pinfunction "8_8") (pintype "passive"))
      (node (ref "U1") (pin "10") (pinfunction "PA0/WKUP/USART2_CTS/ADC12_IN0/TIM2_CH1_ETR_10") (pintype "bidirectional"))
    )
    (net (code "36") (name "/S2") (class "Default")
      (node (ref "R2") (pin "1") (pinfunction "1_1") (pintype "passive"))
      (node (ref "SW1") (pin "7") (pinfunction "7_7") (pintype "passive"))
      (node (ref "U1") (pin "11") (pinfunction "PA1/USART2_RTS/ADC12_IN1/TIM2_CH2_11") (pintype "bidirectional"))
    )
    (net (code "37") (name "/S3") (class "Default")
      (node (ref "R3") (pin "1") (pinfunction "1_1") (pintype "passive"))
      (node (ref "SW1") (pin "6") (pinfunction "6_6") (pintype "passive"))
      (node (ref "U1") (pin "12") (pinfunction "PA2/USART2_TX/ADC12_IN2/TIM2_CH3_12") (pintype "bidirectional"))
    )
    (net (code "38") (name "/S4") (class "Default")
      (node (ref "R4") (pin "1") (pinfunction "1_1") (pintype "passive"))
      (node (ref "SW1") (pin "5") (pinfunction "5_5") (pintype "passive"))
      (node (ref "U1") (pin "29") (pinfunction "PA8/USART1_CK/TIM1_CH1/MCO_29") (pintype "bidirectional"))
    )
    (net (code "39") (name "/SCL") (class "Default")
      (node (ref "LED1") (pin "1") (pinfunction "SCL_1") (pintype "passive"))
      (node (ref "R5") (pin "2") (pinfunction "2_2") (pintype "passive"))
      (node (ref "U1") (pin "42") (pinfunction "PB6/I2C1_SCL/USART1_TX_42") (pintype "bidirectional"))
      (node (ref "X1") (pin "1") (pinfunction "1_1") (pintype "passive"))
    )
    (net (code "40") (name "/SDA") (class "Default")
      (node (ref "LED1") (pin "2") (pinfunction "SDA_2") (pintype "passive"))
      (node (ref "R6") (pin "2") (pinfunction "2_2") (pintype "passive"))
      (node (ref "U1") (pin "43") (pinfunction "PB7/I2C1_SDA/USART1_RX_43") (pintype "bidirectional"))
      (node (ref "X1") (pin "2") (pinfunction "2_2") (pintype "passive"))
    )
    (net (code "41") (name "/SPI_MOSI") (class "Default")
      (node (ref "U1") (pin "17") (pinfunction "PA7/SPI1_MOSI/ADC12_IN7/TIM3_CH2/TIM1_CH1N_17") (pintype "bidirectional"))
      (node (ref "U2") (pin "42") (pinfunction "SIN_42") (pintype "input"))
    )
    (net (code "42") (name "/SPI_SCK") (class "Default")
      (node (ref "U1") (pin "15") (pinfunction "PA5/SPI1_SCK/ADC12_IN5_15") (pintype "bidirectional"))
      (node (ref "U2") (pin "40") (pinfunction "SCLK_40") (pintype "input"))
    )
    (net (code "43") (name "/TCK") (class "Default")
      (node (ref "R16") (pin "1") (pinfunction "1_1") (pintype "passive"))
      (node (ref "U1") (pin "37") (pinfunction "PA14/JTCK/SWCLK/PA14_37") (pintype "bidirectional"))
      (node (ref "X2") (pin "5") (pinfunction "TCK_5") (pintype "output"))
    )
    (net (code "44") (name "/TDI") (class "Default")
      (node (ref "R13") (pin "2") (pinfunction "2_2") (pintype "passive"))
      (node (ref "U1") (pin "38") (pinfunction "PA15/JTDI/TIM2_CH1_ETR/PA15/SPI1_NSS_38") (pintype "bidirectional"))
      (node (ref "X2") (pin "3") (pinfunction "TDI_3") (pintype "input"))
    )
    (net (code "45") (name "/TDO") (class "Default")
      (node (ref "R11") (pin "2") (pinfunction "2_2") (pintype "passive"))
      (node (ref "R15") (pin "1") (pinfunction "1_1") (pintype "passive"))
      (node (ref "U1") (pin "39") (pinfunction "PB3/JTDO/TIM2_CH2/TRACESWO/SPI1_SCK_39") (pintype "bidirectional"))
    )
    (net (code "46") (name "/TMS") (class "Default")
      (node (ref "R12") (pin "2") (pinfunction "2_2") (pintype "passive"))
      (node (ref "U1") (pin "34") (pinfunction "PA13/JTMS/SWDIO/PA13_34") (pintype "bidirectional"))
      (node (ref "X2") (pin "4") (pinfunction "TMS_4") (pintype "output"))
    )
    (net (code "47") (name "/TRST") (class "Default")
      (node (ref "R14") (pin "2") (pinfunction "2_2") (pintype "passive"))
      (node (ref "U1") (pin "40") (pinfunction "PB4/NJTRST/TIM3_CH1/SPI1_MISO_40") (pintype "bidirectional"))
      (node (ref "X2") (pin "2") (pinfunction "TRST_2") (pintype "output"))
    )
    (net (code "48") (name "/UART1_RX") (class "Default")
      (node (ref "U1") (pin "31") (pinfunction "PA10/USART1_RX/TIM1_CH3_31") (pintype "bidirectional+no_connect"))
    )
    (net (code "49") (name "/UART1_TX") (class "Default")
      (node (ref "U1") (pin "30") (pinfunction "PA9/USART1_TX/TIM1_CH2_30") (pintype "bidirectional+no_connect"))
    )
    (net (code "50") (name "/nRST") (class "Default")
      (node (ref "C12") (pin "1") (pinfunction "1_1") (pintype "passive"))
      (node (ref "J1") (pin "1") (pinfunction "1_1") (pintype "passive"))
      (node (ref "R18") (pin "2") (pinfunction "2_2") (pintype "passive"))
      (node (ref "U1") (pin "7") (pinfunction "NRST_7") (pintype "bidirectional"))
      (node (ref "X2") (pin "8") (pinfunction "RESET_8") (pintype "output"))
    )
    (net (code "51") (name "GND") (class "Default")
      (node (ref "C1") (pin "1") (pinfunction "1_1") (pintype "passive"))
      (node (ref "C10") (pin "1") (pinfunction "1_1") (pintype "passive"))
      (node (ref "C11") (pin "1") (pinfunction "1_1") (pintype "passive"))
      (node (ref "C12") (pin "2") (pinfunction "2_2") (pintype "passive"))
      (node (ref "C13") (pin "2") (pinfunction "2_2") (pintype "passive"))
      (node (ref "C14") (pin "2") (pinfunction "2_2") (pintype "passive"))
      (node (ref "C15") (pin "2") (pinfunction "2_2") (pintype "passive"))
      (node (ref "C16") (pin "2") (pinfunction "2_2") (pintype "passive"))
      (node (ref "C18") (pin "1") (pinfunction "1_1") (pintype "passive"))
      (node (ref "C19") (pin "1") (pinfunction "1_1") (pintype "passive"))
      (node (ref "C2") (pin "1") (pinfunction "1_1") (pintype "passive"))
      (node (ref "C20") (pin "1") (pinfunction "1_1") (pintype "passive"))
      (node (ref "C21") (pin "1") (pinfunction "1_1") (pintype "passive"))
      (node (ref "C22") (pin "1") (pinfunction "1_1") (pintype "passive"))
      (node (ref "C23") (pin "1") (pinfunction "1_1") (pintype "passive"))
      (node (ref "C3") (pin "1") (pinfunction "1_1") (pintype "passive"))
      (node (ref "C4") (pin "1") (pinfunction "1_1") (pintype "passive"))
      (node (ref "C5") (pin "1") (pinfunction "1_1") (pintype "passive"))
      (node (ref "C6") (pin "2") (pinfunction "2_2") (pintype "passive"))
      (node (ref "C7") (pin "1") (pinfunction "1_1") (pintype "passive"))
      (node (ref "C8") (pin "1") (pinfunction "1_1") (pintype "passive"))
      (node (ref "C9") (pin "1") (pinfunction "1_1") (pintype "passive"))
      (node (ref "D1") (pin "3") (pintype "passive"))
      (node (ref "D2") (pin "2") (pinfunction "A_2") (pintype "passive"))
      (node (ref "D3") (pin "A") (pinfunction "A_A") (pintype "passive"))
      (node (ref "D4") (pin "2") (pinfunction "A_2") (pintype "passive"))
      (node (ref "J1") (pin "2") (pinfunction "2_2") (pintype "passive"))
      (node (ref "LED1") (pin "3") (pinfunction "GND_3") (pintype "passive"))
      (node (ref "R10") (pin "1") (pinfunction "1_1") (pintype "passive"))
      (node (ref "R16") (pin "2") (pinfunction "2_2") (pintype "passive"))
      (node (ref "R17") (pin "2") (pinfunction "2_2") (pintype "passive"))
      (node (ref "R22") (pin "1") (pinfunction "1_1") (pintype "passive"))
      (node (ref "R23") (pin "1") (pinfunction "1_1") (pintype "passive"))
      (node (ref "R24") (pin "1") (pinfunction "1_1") (pintype "passive"))
      (node (ref "R7") (pin "1") (pinfunction "1_1") (pintype "passive"))
      (node (ref "R8") (pin "1") (pinfunction "1_1") (pintype "passive"))
      (node (ref "R9") (pin "2") (pinfunction "2_2") (pintype "passive"))
      (node (ref "SW1") (pin "1") (pinfunction "1_1") (pintype "passive"))
      (node (ref "SW1") (pin "2") (pinfunction "2_2") (pintype "passive"))
      (node (ref "SW1") (pin "3") (pinfunction "3_3") (pintype "passive"))
      (node (ref "SW1") (pin "4") (pinfunction "4_4") (pintype "passive"))
      (node (ref "U1") (pin "23") (pinfunction "Vss_1_23") (pintype "power_in"))
      (node (ref "U1") (pin "35") (pinfunction "Vss_2_35") (pintype "power_in"))
      (node (ref "U1") (pin "47") (pinfunction "Vss_3_47") (pintype "power_in"))
      (node (ref "U1") (pin "8") (pinfunction "Vssa_8") (pintype "power_in"))
      (node (ref "U2") (pin "21") (pinfunction "GNDANA_21") (pintype "power_in"))
      (node (ref "U2") (pin "37") (pinfunction "GNDLOG_37") (pintype "power_in"))
      (node (ref "U2") (pin "43") (pinfunction "GNDLED_43") (pintype "power_in"))
      (node (ref "U2") (pin "48") (pinfunction "GNDLED_48") (pintype "power_in"))
      (node (ref "U2") (pin "5") (pinfunction "GNDLED_5") (pintype "power_in"))
      (node (ref "U3") (pin "6") (pinfunction "GND_6") (pintype "passive"))
      (node (ref "U3") (pin "9") (pinfunction "Pad_9") (pintype "passive"))
      (node (ref "U4") (pin "2") (pinfunction "GND_2") (pintype "power_in"))
      (node (ref "U4") (pin "8") (pinfunction "RS_8") (pintype "input"))
      (node (ref "X1") (pin "3") (pinfunction "3_3") (pintype "passive"))
      (node (ref "X12") (pin "2") (pinfunction "2_2") (pintype "passive"))
      (node (ref "X2") (pin "1") (pinfunction "GND_1") (pintype "power_in"))
      (node (ref "X2") (pin "10") (pinfunction "GND_10") (pintype "power_in"))
      (node (ref "X4") (pin "3") (pinfunction "3_3") (pintype "passive"))
      (node (ref "X5") (pin "3") (pinfunction "3_3") (pintype "passive"))
      (node (ref "Z1") (pin "2") (pinfunction "2_2") (pintype "passive"))
      (node (ref "Z1") (pin "4") (pinfunction "4_4") (pintype "passive"))
    )
    (net (code "52") (name "Net-(D4-C)") (class "Default")
      (node (ref "C14") (pin "1") (pinfunction "1_1") (pintype "passive"))
      (node (ref "C15") (pin "1") (pinfunction "1_1") (pintype "passive"))
      (node (ref "D4") (pin "1") (pinfunction "C_1") (pintype "passive"))
      (node (ref "F1") (pin "2") (pinfunction "2_2") (pintype "passive"))
      (node (ref "R19") (pin "2") (pinfunction "2_2") (pintype "passive"))
      (node (ref "U3") (pin "7") (pinfunction "VIN_7") (pintype "passive"))
    )
    (net (code "53") (name "Net-(F1-Pad1)") (class "Default")
      (node (ref "F1") (pin "1") (pinfunction "1_1") (pintype "passive"))
      (node (ref "X12") (pin "1") (pinfunction "1_1") (pintype "passive"))
    )
    (net (code "54") (name "Net-(J2-Pad2)") (class "Default")
      (node (ref "J2") (pin "2") (pinfunction "2_2") (pintype "passive"))
      (node (ref "R21") (pin "1") (pinfunction "1_1") (pintype "passive"))
    )
    (net (code "55") (name "Net-(U1-PB2{slash}BOOT1)") (class "Default")
      (node (ref "R7") (pin "2") (pinfunction "2_2") (pintype "passive"))
      (node (ref "U1") (pin "20") (pinfunction "PB2/BOOT1_20") (pintype "bidirectional"))
    )
    (net (code "56") (name "Net-(U1-PD0{slash}OSC_IN)") (class "Default")
      (node (ref "C6") (pin "1") (pinfunction "1_1") (pintype "passive"))
      (node (ref "U1") (pin "5") (pinfunction "PD0/OSC_IN_5") (pintype "bidirectional"))
      (node (ref "Z1") (pin "1") (pinfunction "1_1") (pintype "passive"))
    )
    (net (code "57") (name "Net-(U1-PD1{slash}OSC_OUT)") (class "Default")
      (node (ref "C7") (pin "2") (pinfunction "2_2") (pintype "passive"))
      (node (ref "U1") (pin "6") (pinfunction "PD1/OSC_OUT_6") (pintype "bidirectional"))
      (node (ref "Z1") (pin "3") (pinfunction "3_3") (pintype "passive"))
    )
    (net (code "58") (name "Net-(U2-IREF)") (class "Default")
      (node (ref "R10") (pin "2") (pinfunction "2_2") (pintype "passive"))
      (node (ref "U2") (pin "17") (pinfunction "IREF_17") (pintype "power_in"))
    )
    (net (code "59") (name "Net-(U3-BOOT)") (class "Default")
      (node (ref "C17") (pin "2") (pinfunction "2_2") (pintype "passive"))
      (node (ref "U3") (pin "1") (pinfunction "BOOT_1") (pintype "passive"))
    )
    (net (code "60") (name "Net-(U3-EN)") (class "Default")
      (node (ref "R19") (pin "1") (pinfunction "1_1") (pintype "passive"))
      (node (ref "U3") (pin "5") (pinfunction "EN_5") (pintype "passive"))
    )
    (net (code "61") (name "Net-(U3-FB)") (class "Default")
      (node (ref "R20") (pin "1") (pinfunction "1_1") (pintype "passive"))
      (node (ref "R22") (pin "2") (pinfunction "2_2") (pintype "passive"))
      (node (ref "U3") (pin "4") (pinfunction "FB_4") (pintype "passive"))
    )
    (net (code "62") (name "Net-(U3-RT{slash}SYNC)") (class "Default")
      (node (ref "R23") (pin "2") (pinfunction "2_2") (pintype "passive"))
      (node (ref "U3") (pin "3") (pinfunction "RT/SYNC_3") (pintype "passive"))
    )
    (net (code "63") (name "Net-(U3-SS)") (class "Default")
      (node (ref "C23") (pin "2") (pinfunction "2_2") (pintype "passive"))
      (node (ref "U3") (pin "2") (pinfunction "SS_2") (pintype "passive"))
    )
    (net (code "64") (name "Net-(U3-SW)") (class "Default")
      (node (ref "C17") (pin "1") (pinfunction "1_1") (pintype "passive"))
      (node (ref "D3") (pin "K") (pinfunction "K_K") (pintype "passive"))
      (node (ref "L1") (pin "1") (pinfunction "1_1") (pintype "passive"))
      (node (ref "U3") (pin "8") (pinfunction "SW_8") (pintype "passive"))
    )
    (net (code "65") (name "Net-(U4-CANH)") (class "Default")
      (node (ref "R21") (pin "2") (pinfunction "2_2") (pintype "passive"))
      (node (ref "U4") (pin "7") (pinfunction "CANH_7") (pintype "bidirectional"))
      (node (ref "X4") (pin "1") (pinfunction "1_1") (pintype "passive"))
      (node (ref "X5") (pin "1") (pinfunction "1_1") (pintype "passive"))
    )
    (net (code "66") (name "Net-(U4-CANL)") (class "Default")
      (node (ref "J2") (pin "1") (pinfunction "1_1") (pintype "passive"))
      (node (ref "U4") (pin "6") (pinfunction "CANL_6") (pintype "bidirectional"))
      (node (ref "X4") (pin "2") (pinfunction "2_2") (pintype "passive"))
      (node (ref "X5") (pin "2") (pinfunction "2_2") (pintype "passive"))
    )
    (net (code "67") (name "Net-(U5-GND)") (class "Default")
      (node (ref "R24") (pin "2") (pinfunction "2_2") (pintype "passive"))
      (node (ref "U5") (pin "1") (pinfunction "GND_1") (pintype "power_in"))
    )
    (net (code "68") (name "Net-(X2-RTCK)") (class "Default")
      (node (ref "R17") (pin "1") (pinfunction "1_1") (pintype "passive"))
      (node (ref "X2") (pin "6") (pinfunction "RTCK_6") (pintype "passive"))
    )
    (net (code "69") (name "Net-(X2-TDO)") (class "Default")
      (node (ref "R15") (pin "2") (pinfunction "2_2") (pintype "passive"))
      (node (ref "X2") (pin "7") (pinfunction "TDO_7") (pintype "output"))
    )
    (net (code "70") (name "VLED") (class "Default")
      (node (ref "C10") (pin "2") (pinfunction "2_2") (pintype "passive"))
      (node (ref "C11") (pin "2") (pinfunction "2_2") (pintype "passive"))
      (node (ref "C18") (pin "2") (pinfunction "2_2") (pintype "passive"))
      (node (ref "C19") (pin "2") (pinfunction "2_2") (pintype "passive"))
      (node (ref "C20") (pin "2") (pinfunction "2_2") (pintype "passive"))
      (node (ref "C8") (pin "2") (pinfunction "2_2") (pintype "passive"))
      (node (ref "C9") (pin "2") (pinfunction "2_2") (pintype "passive"))
      (node (ref "D2") (pin "1") (pinfunction "C_1") (pintype "passive"))
      (node (ref "L1") (pin "2") (pinfunction "2_2") (pintype "passive"))
      (node (ref "LED1") (pin "4") (pinfunction "VCC_4") (pintype "passive"))
      (node (ref "R20") (pin "2") (pinfunction "2_2") (pintype "passive"))
      (node (ref "U2") (pin "18") (pinfunction "VLED_18") (pintype "power_in"))
      (node (ref "U2") (pin "19") (pinfunction "VANA_19") (pintype "power_in"))
      (node (ref "U2") (pin "31") (pinfunction "VLED_31") (pintype "power_in"))
      (node (ref "U2") (pin "34") (pinfunction "VLOG_34") (pintype "power_in"))
      (node (ref "U2") (pin "8") (pinfunction "VLED_8") (pintype "power_in"))
      (node (ref "U5") (pin "3") (pinfunction "IN_3") (pintype "power_in"))
      (node (ref "X1") (pin "4") (pinfunction "4_4") (pintype "passive"))
    )
    (net (code "71") (name "unconnected-(U1-PA6{slash}SPI1_MISO{slash}ADC12_IN6{slash}TIM3_CH1{slash}TIM1_BKIN-Pad16)") (class "Default")
      (node (ref "U1") (pin "16") (pinfunction "PA6/SPI1_MISO/ADC12_IN6/TIM3_CH1/TIM1_BKIN_16") (pintype "bidirectional"))
    )
    (net (code "72") (name "unconnected-(U1-PB0{slash}ADC12_IN8{slash}TIM3_CH3{slash}TIM1_CH2N-Pad18)") (class "Default")
      (node (ref "U1") (pin "18") (pinfunction "PB0/ADC12_IN8/TIM3_CH3/TIM1_CH2N_18") (pintype "bidirectional"))
    )
    (net (code "73") (name "unconnected-(U1-PB1{slash}ADC12_IN9{slash}TIM3_CH4{slash}TIM1_CH3N-Pad19)") (class "Default")
      (node (ref "U1") (pin "19") (pinfunction "PB1/ADC12_IN9/TIM3_CH4/TIM1_CH3N_19") (pintype "bidirectional"))
    )
    (net (code "74") (name "unconnected-(U1-PB5{slash}I2C1_SMBA{slash}TIM3_CH2{slash}SPI1_MOSI-Pad41)") (class "Default")
      (node (ref "U1") (pin "41") (pinfunction "PB5/I2C1_SMBA/TIM3_CH2/SPI1_MOSI_41") (pintype "bidirectional"))
    )
    (net (code "75") (name "unconnected-(U1-PB11{slash}TIM2_CH4-Pad22)") (class "Default")
      (node (ref "U1") (pin "22") (pinfunction "PB11/TIM2_CH4_22") (pintype "bidirectional"))
    )
    (net (code "76") (name "unconnected-(U1-PB12{slash}TIM1_BKIN-Pad25)") (class "Default")
      (node (ref "U1") (pin "25") (pinfunction "PB12/TIM1_BKIN_25") (pintype "bidirectional"))
    )
    (net (code "77") (name "unconnected-(U1-PB13{slash}TIM1_CH1N-Pad26)") (class "Default")
      (node (ref "U1") (pin "26") (pinfunction "PB13/TIM1_CH1N_26") (pintype "bidirectional"))
    )
    (net (code "78") (name "unconnected-(U1-PB14{slash}TIM1_CH2N-Pad27)") (class "Default")
      (node (ref "U1") (pin "27") (pinfunction "PB14/TIM1_CH2N_27") (pintype "bidirectional"))
    )
    (net (code "79") (name "unconnected-(U1-PB15{slash}TIM1_CH3N-Pad28)") (class "Default")
      (node (ref "U1") (pin "28") (pinfunction "PB15/TIM1_CH3N_28") (pintype "bidirectional"))
    )
    (net (code "80") (name "unconnected-(U1-PC13{slash}TAMPER-RTC-Pad2)") (class "Default")
      (node (ref "U1") (pin "2") (pinfunction "PC13/TAMPER-RTC_2") (pintype "bidirectional"))
    )
    (net (code "81") (name "unconnected-(U1-PC14{slash}OSC32_IN-Pad3)") (class "Default")
      (node (ref "U1") (pin "3") (pinfunction "PC14/OSC32_IN_3") (pintype "bidirectional"))
    )
    (net (code "82") (name "unconnected-(U1-PC15{slash}OSC32_OUT-Pad4)") (class "Default")
      (node (ref "U1") (pin "4") (pinfunction "PC15/OSC32_OUT_4") (pintype "bidirectional"))
    )
    (net (code "83") (name "unconnected-(U2-DSEL-Pad30)") (class "Default")
      (node (ref "U2") (pin "30") (pinfunction "DSEL_30") (pintype "passive+no_connect"))
    )
    (net (code "84") (name "unconnected-(U2-NC-Pad6)") (class "Default")
      (node (ref "U2") (pin "6") (pinfunction "NC_6") (pintype "power_in"))
    )
    (net (code "85") (name "unconnected-(U2-NC-Pad7)") (class "Default")
      (node (ref "U2") (pin "7") (pinfunction "NC_7") (pintype "power_in"))
    )
    (net (code "86") (name "unconnected-(U2-NC-Pad20)") (class "Default")
      (node (ref "U2") (pin "20") (pinfunction "NC_20") (pintype "power_in"))
    )
    (net (code "87") (name "unconnected-(U2-SOUT-Pad32)") (class "Default")
      (node (ref "U2") (pin "32") (pinfunction "SOUT_32") (pintype "output+no_connect"))
    )
    (net (code "88") (name "unconnected-(U4-VREF-Pad5)") (class "Default")
      (node (ref "U4") (pin "5") (pinfunction "VREF_5") (pintype "passive"))
    )
  )
)
